# Microscope_LED_Ring_Light.net
KiCad netlist of a schematic drawn in EAGLE
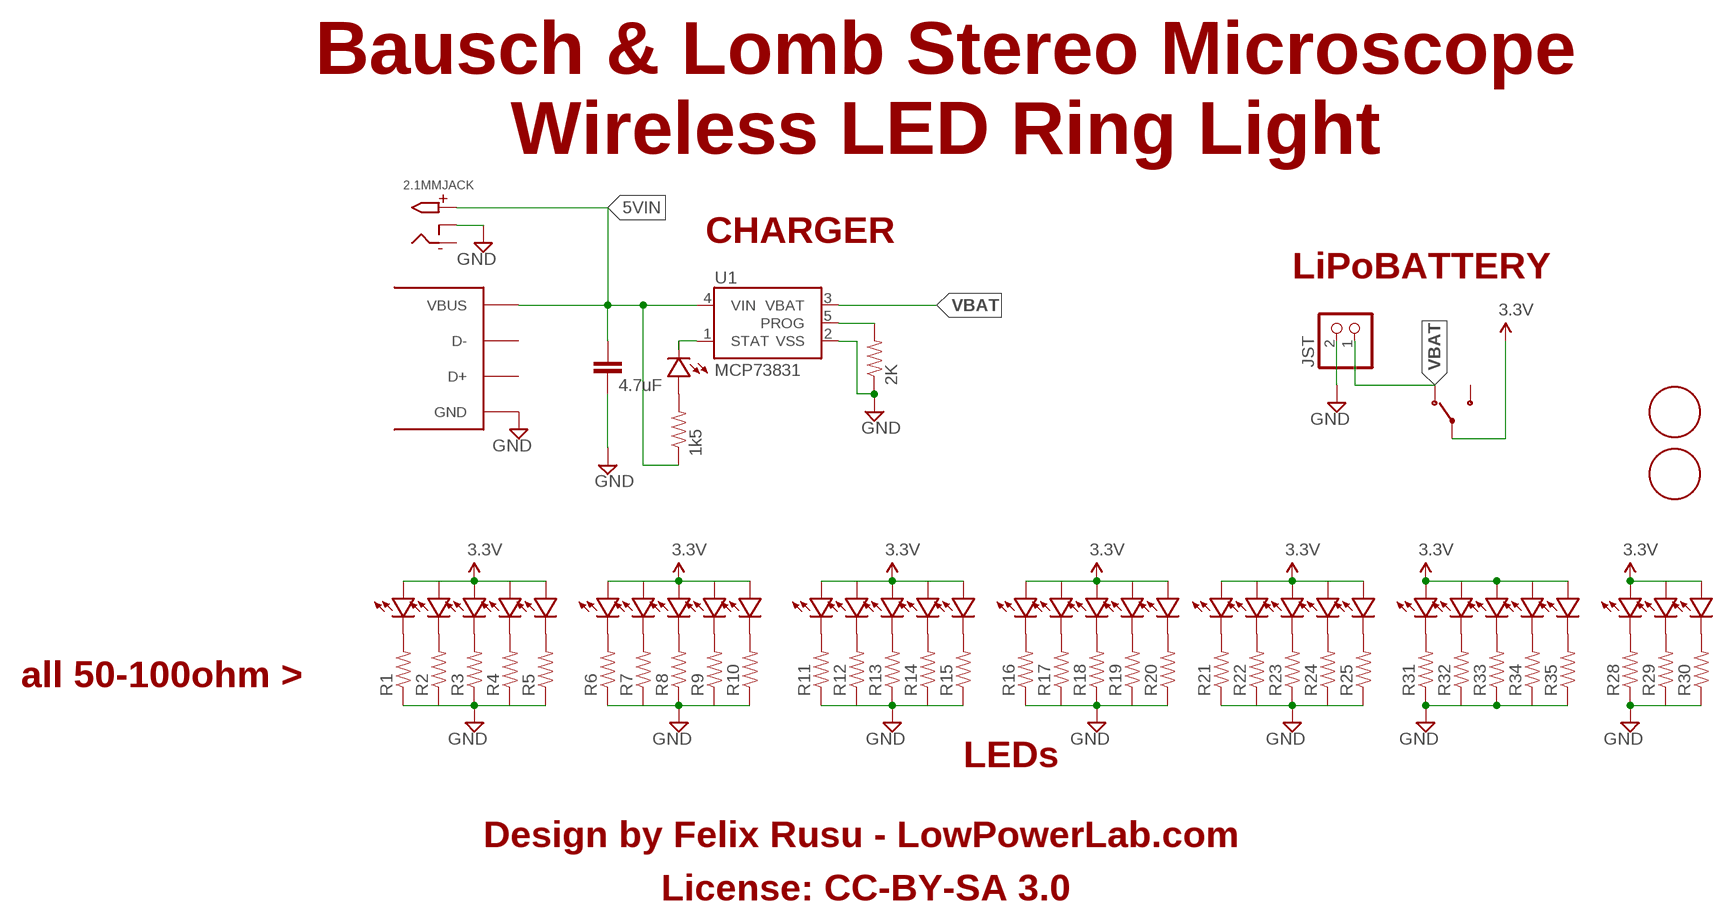
[diagram p0: schematic, sheet 1]

(export (version "E")
  (design (tool "Eeschema 10.0.6"))
  (components
    (comp (ref "2.1MMJACK")
      (value "2.1MMJACKSLOTS")
      (footprint "eagle-import:2.1MM_JACK_SLOTS")
      (libsource (lib "eagle-import") (part "2.1MMJACKSLOTS"))
    )
    (comp (ref "C1")
      (value "4.7uF")
      (footprint "eagle-import:0603-CAP")
      (libsource (lib "eagle-import") (part "CAP0603-CAP"))
    )
    (comp (ref "FIDUCIAL_BOTTOMRIGHT")
      (value "FIDUCIAL1.5MM")
      (footprint "eagle-import:FIDUCIAL_1.5MM")
      (libsource (lib "eagle-import") (part "FIDUCIAL1.5MM"))
    )
    (comp (ref "FIDUCIAL_TOPLEFT")
      (value "FIDUCIAL1.5MM")
      (footprint "eagle-import:FIDUCIAL_1.5MM")
      (libsource (lib "eagle-import") (part "FIDUCIAL1.5MM"))
    )
    (comp (ref "JST")
      (value "JST_2PIN-SMT-RA")
      (footprint "eagle-import:JST-PH-2-SMT-RA")
      (libsource (lib "eagle-import") (part "JST_2PIN-SMT-RA"))
    )
    (comp (ref "R1")
      (value "RESISTOR0805")
      (footprint "eagle-import:0805")
      (libsource (lib "eagle-import") (part "RESISTOR0805"))
    )
    (comp (ref "R2")
      (value "RESISTOR0805")
      (footprint "eagle-import:0805")
      (libsource (lib "eagle-import") (part "RESISTOR0805"))
    )
    (comp (ref "R3")
      (value "RESISTOR0805")
      (footprint "eagle-import:0805")
      (libsource (lib "eagle-import") (part "RESISTOR0805"))
    )
    (comp (ref "R4")
      (value "RESISTOR0805")
      (footprint "eagle-import:0805")
      (libsource (lib "eagle-import") (part "RESISTOR0805"))
    )
    (comp (ref "R5")
      (value "RESISTOR0805")
      (footprint "eagle-import:0805")
      (libsource (lib "eagle-import") (part "RESISTOR0805"))
    )
    (comp (ref "R6")
      (value "RESISTOR0805")
      (footprint "eagle-import:0805")
      (libsource (lib "eagle-import") (part "RESISTOR0805"))
    )
    (comp (ref "R7")
      (value "RESISTOR0805")
      (footprint "eagle-import:0805")
      (libsource (lib "eagle-import") (part "RESISTOR0805"))
    )
    (comp (ref "R8")
      (value "RESISTOR0805")
      (footprint "eagle-import:0805")
      (libsource (lib "eagle-import") (part "RESISTOR0805"))
    )
    (comp (ref "R9")
      (value "RESISTOR0805")
      (footprint "eagle-import:0805")
      (libsource (lib "eagle-import") (part "RESISTOR0805"))
    )
    (comp (ref "R10")
      (value "RESISTOR0805")
      (footprint "eagle-import:0805")
      (libsource (lib "eagle-import") (part "RESISTOR0805"))
    )
    (comp (ref "R11")
      (value "RESISTOR0805")
      (footprint "eagle-import:0805")
      (libsource (lib "eagle-import") (part "RESISTOR0805"))
    )
    (comp (ref "R12")
      (value "RESISTOR0805")
      (footprint "eagle-import:0805")
      (libsource (lib "eagle-import") (part "RESISTOR0805"))
    )
    (comp (ref "R13")
      (value "RESISTOR0805")
      (footprint "eagle-import:0805")
      (libsource (lib "eagle-import") (part "RESISTOR0805"))
    )
    (comp (ref "R14")
      (value "RESISTOR0805")
      (footprint "eagle-import:0805")
      (libsource (lib "eagle-import") (part "RESISTOR0805"))
    )
    (comp (ref "R15")
      (value "RESISTOR0805")
      (footprint "eagle-import:0805")
      (libsource (lib "eagle-import") (part "RESISTOR0805"))
    )
    (comp (ref "R16")
      (value "RESISTOR0805")
      (footprint "eagle-import:0805")
      (libsource (lib "eagle-import") (part "RESISTOR0805"))
    )
    (comp (ref "R17")
      (value "RESISTOR0805")
      (footprint "eagle-import:0805")
      (libsource (lib "eagle-import") (part "RESISTOR0805"))
    )
    (comp (ref "R18")
      (value "RESISTOR0805")
      (footprint "eagle-import:0805")
      (libsource (lib "eagle-import") (part "RESISTOR0805"))
    )
    (comp (ref "R19")
      (value "RESISTOR0805")
      (footprint "eagle-import:0805")
      (libsource (lib "eagle-import") (part "RESISTOR0805"))
    )
    (comp (ref "R20")
      (value "RESISTOR0805")
      (footprint "eagle-import:0805")
      (libsource (lib "eagle-import") (part "RESISTOR0805"))
    )
    (comp (ref "R21")
      (value "RESISTOR0805")
      (footprint "eagle-import:0805")
      (libsource (lib "eagle-import") (part "RESISTOR0805"))
    )
    (comp (ref "R22")
      (value "RESISTOR0805")
      (footprint "eagle-import:0805")
      (libsource (lib "eagle-import") (part "RESISTOR0805"))
    )
    (comp (ref "R23")
      (value "RESISTOR0805")
      (footprint "eagle-import:0805")
      (libsource (lib "eagle-import") (part "RESISTOR0805"))
    )
    (comp (ref "R24")
      (value "RESISTOR0805")
      (footprint "eagle-import:0805")
      (libsource (lib "eagle-import") (part "RESISTOR0805"))
    )
    (comp (ref "R25")
      (value "RESISTOR0805")
      (footprint "eagle-import:0805")
      (libsource (lib "eagle-import") (part "RESISTOR0805"))
    )
    (comp (ref "R26")
      (value "1k5")
      (footprint "eagle-import:0603-RES")
      (libsource (lib "eagle-import") (part "RESISTOR0603-RES"))
    )
    (comp (ref "R27")
      (value "2K")
      (footprint "eagle-import:0603-RES")
      (libsource (lib "eagle-import") (part "RESISTOR0603-RES"))
    )
    (comp (ref "R28")
      (value "RESISTOR0805")
      (footprint "eagle-import:0805")
      (libsource (lib "eagle-import") (part "RESISTOR0805"))
    )
    (comp (ref "R29")
      (value "RESISTOR0805")
      (footprint "eagle-import:0805")
      (libsource (lib "eagle-import") (part "RESISTOR0805"))
    )
    (comp (ref "R30")
      (value "RESISTOR0805")
      (footprint "eagle-import:0805")
      (libsource (lib "eagle-import") (part "RESISTOR0805"))
    )
    (comp (ref "R31")
      (value "RESISTOR0805")
      (footprint "eagle-import:0805")
      (libsource (lib "eagle-import") (part "RESISTOR0805"))
    )
    (comp (ref "R32")
      (value "RESISTOR0805")
      (footprint "eagle-import:0805")
      (libsource (lib "eagle-import") (part "RESISTOR0805"))
    )
    (comp (ref "R33")
      (value "RESISTOR0805")
      (footprint "eagle-import:0805")
      (libsource (lib "eagle-import") (part "RESISTOR0805"))
    )
    (comp (ref "R34")
      (value "RESISTOR0805")
      (footprint "eagle-import:0805")
      (libsource (lib "eagle-import") (part "RESISTOR0805"))
    )
    (comp (ref "R35")
      (value "RESISTOR0805")
      (footprint "eagle-import:0805")
      (libsource (lib "eagle-import") (part "RESISTOR0805"))
    )
    (comp (ref "U$1")
      (value "LED")
      (footprint "eagle-import:LED_2.8X3.3MM")
      (libsource (lib "eagle-import") (part "LED"))
    )
    (comp (ref "U$2")
      (value "LED")
      (footprint "eagle-import:LED_2.8X3.3MM")
      (libsource (lib "eagle-import") (part "LED"))
    )
    (comp (ref "U$3")
      (value "LED")
      (footprint "eagle-import:LED_2.8X3.3MM")
      (libsource (lib "eagle-import") (part "LED"))
    )
    (comp (ref "U$4")
      (value "LED")
      (footprint "eagle-import:LED_2.8X3.3MM")
      (libsource (lib "eagle-import") (part "LED"))
    )
    (comp (ref "U$5")
      (value "LED")
      (footprint "eagle-import:LED_2.8X3.3MM")
      (libsource (lib "eagle-import") (part "LED"))
    )
    (comp (ref "U$6")
      (value "LED")
      (footprint "eagle-import:LED_2.8X3.3MM")
      (libsource (lib "eagle-import") (part "LED"))
    )
    (comp (ref "U$7")
      (value "LED")
      (footprint "eagle-import:LED_2.8X3.3MM")
      (libsource (lib "eagle-import") (part "LED"))
    )
    (comp (ref "U$8")
      (value "LED")
      (footprint "eagle-import:LED_2.8X3.3MM")
      (libsource (lib "eagle-import") (part "LED"))
    )
    (comp (ref "U$9")
      (value "LED")
      (footprint "eagle-import:LED_2.8X3.3MM")
      (libsource (lib "eagle-import") (part "LED"))
    )
    (comp (ref "U$10")
      (value "LED")
      (footprint "eagle-import:LED_2.8X3.3MM")
      (libsource (lib "eagle-import") (part "LED"))
    )
    (comp (ref "U$11")
      (value "LED")
      (footprint "eagle-import:LED_2.8X3.3MM")
      (libsource (lib "eagle-import") (part "LED"))
    )
    (comp (ref "U$12")
      (value "LED")
      (footprint "eagle-import:LED_2.8X3.3MM")
      (libsource (lib "eagle-import") (part "LED"))
    )
    (comp (ref "U$13")
      (value "LED")
      (footprint "eagle-import:LED_2.8X3.3MM")
      (libsource (lib "eagle-import") (part "LED"))
    )
    (comp (ref "U$14")
      (value "LED")
      (footprint "eagle-import:LED_2.8X3.3MM")
      (libsource (lib "eagle-import") (part "LED"))
    )
    (comp (ref "U$15")
      (value "LED")
      (footprint "eagle-import:LED_2.8X3.3MM")
      (libsource (lib "eagle-import") (part "LED"))
    )
    (comp (ref "U$16")
      (value "LED")
      (footprint "eagle-import:LED_2.8X3.3MM")
      (libsource (lib "eagle-import") (part "LED"))
    )
    (comp (ref "U$17")
      (value "LED")
      (footprint "eagle-import:LED_2.8X3.3MM")
      (libsource (lib "eagle-import") (part "LED"))
    )
    (comp (ref "U$18")
      (value "LED")
      (footprint "eagle-import:LED_2.8X3.3MM")
      (libsource (lib "eagle-import") (part "LED"))
    )
    (comp (ref "U$19")
      (value "LED")
      (footprint "eagle-import:LED_2.8X3.3MM")
      (libsource (lib "eagle-import") (part "LED"))
    )
    (comp (ref "U$20")
      (value "LED")
      (footprint "eagle-import:LED_2.8X3.3MM")
      (libsource (lib "eagle-import") (part "LED"))
    )
    (comp (ref "U$21")
      (value "LED")
      (footprint "eagle-import:LED_2.8X3.3MM")
      (libsource (lib "eagle-import") (part "LED"))
    )
    (comp (ref "U$22")
      (value "LED")
      (footprint "eagle-import:LED_2.8X3.3MM")
      (libsource (lib "eagle-import") (part "LED"))
    )
    (comp (ref "U$23")
      (value "LED")
      (footprint "eagle-import:LED_2.8X3.3MM")
      (libsource (lib "eagle-import") (part "LED"))
    )
    (comp (ref "U$24")
      (value "LED")
      (footprint "eagle-import:LED_2.8X3.3MM")
      (libsource (lib "eagle-import") (part "LED"))
    )
    (comp (ref "U$25")
      (value "LED")
      (footprint "eagle-import:LED_2.8X3.3MM")
      (libsource (lib "eagle-import") (part "LED"))
    )
    (comp (ref "U$26")
      (value "USB_4PIN2PINS_SLOTTED")
      (footprint "eagle-import:USB-B-MICRO_2PADS_SLOTS")
      (libsource (lib "eagle-import") (part "USB_4PIN2PINS_SLOTTED"))
    )
    (comp (ref "U$27")
      (value "SWITCH_SPDT")
      (footprint "eagle-import:SWITCH-SPDT_CKN9560")
      (libsource (lib "eagle-import") (part "SWITCH_SPDT"))
    )
    (comp (ref "U$28")
      (value "LED0603")
      (footprint "eagle-import:0603-LED")
      (libsource (lib "eagle-import") (part "LED0603"))
    )
    (comp (ref "U$29")
      (value "LED")
      (footprint "eagle-import:LED_2.8X3.3MM")
      (libsource (lib "eagle-import") (part "LED"))
    )
    (comp (ref "U$30")
      (value "LED")
      (footprint "eagle-import:LED_2.8X3.3MM")
      (libsource (lib "eagle-import") (part "LED"))
    )
    (comp (ref "U$31")
      (value "LED")
      (footprint "eagle-import:LED_2.8X3.3MM")
      (libsource (lib "eagle-import") (part "LED"))
    )
    (comp (ref "U$32")
      (value "LED")
      (footprint "eagle-import:LED_2.8X3.3MM")
      (libsource (lib "eagle-import") (part "LED"))
    )
    (comp (ref "U$33")
      (value "LED")
      (footprint "eagle-import:LED_2.8X3.3MM")
      (libsource (lib "eagle-import") (part "LED"))
    )
    (comp (ref "U$34")
      (value "LED")
      (footprint "eagle-import:LED_2.8X3.3MM")
      (libsource (lib "eagle-import") (part "LED"))
    )
    (comp (ref "U$35")
      (value "LED")
      (footprint "eagle-import:LED_2.8X3.3MM")
      (libsource (lib "eagle-import") (part "LED"))
    )
    (comp (ref "U$36")
      (value "LED")
      (footprint "eagle-import:LED_2.8X3.3MM")
      (libsource (lib "eagle-import") (part "LED"))
    )
    (comp (ref "U1")
      (value "MCP73831")
      (footprint "eagle-import:SOT23-5")
      (libsource (lib "eagle-import") (part "MCP73831"))
    )
  )
  (nets
    (net (code "1") (name "3.3V") (class "Default")
      (node (ref "U$1") (pin "PLUS") (pinfunction "PLUS_PLUS") (pintype "passive"))
      (node (ref "U$10") (pin "PLUS") (pinfunction "PLUS_PLUS") (pintype "passive"))
      (node (ref "U$11") (pin "PLUS") (pinfunction "PLUS_PLUS") (pintype "passive"))
      (node (ref "U$12") (pin "PLUS") (pinfunction "PLUS_PLUS") (pintype "passive"))
      (node (ref "U$13") (pin "PLUS") (pinfunction "PLUS_PLUS") (pintype "passive"))
      (node (ref "U$14") (pin "PLUS") (pinfunction "PLUS_PLUS") (pintype "passive"))
      (node (ref "U$15") (pin "PLUS") (pinfunction "PLUS_PLUS") (pintype "passive"))
      (node (ref "U$16") (pin "PLUS") (pinfunction "PLUS_PLUS") (pintype "passive"))
      (node (ref "U$17") (pin "PLUS") (pinfunction "PLUS_PLUS") (pintype "passive"))
      (node (ref "U$18") (pin "PLUS") (pinfunction "PLUS_PLUS") (pintype "passive"))
      (node (ref "U$19") (pin "PLUS") (pinfunction "PLUS_PLUS") (pintype "passive"))
      (node (ref "U$2") (pin "PLUS") (pinfunction "PLUS_PLUS") (pintype "passive"))
      (node (ref "U$20") (pin "PLUS") (pinfunction "PLUS_PLUS") (pintype "passive"))
      (node (ref "U$21") (pin "PLUS") (pinfunction "PLUS_PLUS") (pintype "passive"))
      (node (ref "U$22") (pin "PLUS") (pinfunction "PLUS_PLUS") (pintype "passive"))
      (node (ref "U$23") (pin "PLUS") (pinfunction "PLUS_PLUS") (pintype "passive"))
      (node (ref "U$24") (pin "PLUS") (pinfunction "PLUS_PLUS") (pintype "passive"))
      (node (ref "U$25") (pin "PLUS") (pinfunction "PLUS_PLUS") (pintype "passive"))
      (node (ref "U$27") (pin "2") (pinfunction "2_2") (pintype "bidirectional"))
      (node (ref "U$29") (pin "PLUS") (pinfunction "PLUS_PLUS") (pintype "passive"))
      (node (ref "U$3") (pin "PLUS") (pinfunction "PLUS_PLUS") (pintype "passive"))
      (node (ref "U$30") (pin "PLUS") (pinfunction "PLUS_PLUS") (pintype "passive"))
      (node (ref "U$31") (pin "PLUS") (pinfunction "PLUS_PLUS") (pintype "passive"))
      (node (ref "U$32") (pin "PLUS") (pinfunction "PLUS_PLUS") (pintype "passive"))
      (node (ref "U$33") (pin "PLUS") (pinfunction "PLUS_PLUS") (pintype "passive"))
      (node (ref "U$34") (pin "PLUS") (pinfunction "PLUS_PLUS") (pintype "passive"))
      (node (ref "U$35") (pin "PLUS") (pinfunction "PLUS_PLUS") (pintype "passive"))
      (node (ref "U$36") (pin "PLUS") (pinfunction "PLUS_PLUS") (pintype "passive"))
      (node (ref "U$4") (pin "PLUS") (pinfunction "PLUS_PLUS") (pintype "passive"))
      (node (ref "U$5") (pin "PLUS") (pinfunction "PLUS_PLUS") (pintype "passive"))
      (node (ref "U$6") (pin "PLUS") (pinfunction "PLUS_PLUS") (pintype "passive"))
      (node (ref "U$7") (pin "PLUS") (pinfunction "PLUS_PLUS") (pintype "passive"))
      (node (ref "U$8") (pin "PLUS") (pinfunction "PLUS_PLUS") (pintype "passive"))
      (node (ref "U$9") (pin "PLUS") (pinfunction "PLUS_PLUS") (pintype "passive"))
    )
    (net (code "2") (name "5VIN") (class "Default")
      (node (ref "2.1MMJACK") (pin "TIP") (pinfunction "TIP_TIP") (pintype "bidirectional"))
      (node (ref "C1") (pin "1") (pinfunction "1_1") (pintype "passive"))
      (node (ref "R26") (pin "1") (pinfunction "1_1") (pintype "passive"))
      (node (ref "U$26") (pin "VBUS") (pinfunction "VBUS_VBUS") (pintype "bidirectional"))
      (node (ref "U1") (pin "4") (pinfunction "VIN_4") (pintype "power_in"))
    )
    (net (code "3") (name "GND") (class "Default")
      (node (ref "2.1MMJACK") (pin "SIDE") (pinfunction "RING_SW_SIDE") (pintype "bidirectional"))
      (node (ref "C1") (pin "2") (pinfunction "2_2") (pintype "passive"))
      (node (ref "JST") (pin "2") (pinfunction "1_2") (pintype "passive"))
      (node (ref "R1") (pin "1") (pinfunction "1_1") (pintype "passive"))
      (node (ref "R10") (pin "1") (pinfunction "1_1") (pintype "passive"))
      (node (ref "R11") (pin "1") (pinfunction "1_1") (pintype "passive"))
      (node (ref "R12") (pin "1") (pinfunction "1_1") (pintype "passive"))
      (node (ref "R13") (pin "1") (pinfunction "1_1") (pintype "passive"))
      (node (ref "R14") (pin "1") (pinfunction "1_1") (pintype "passive"))
      (node (ref "R15") (pin "1") (pinfunction "1_1") (pintype "passive"))
      (node (ref "R16") (pin "1") (pinfunction "1_1") (pintype "passive"))
      (node (ref "R17") (pin "1") (pinfunction "1_1") (pintype "passive"))
      (node (ref "R18") (pin "1") (pinfunction "1_1") (pintype "passive"))
      (node (ref "R19") (pin "1") (pinfunction "1_1") (pintype "passive"))
      (node (ref "R2") (pin "1") (pinfunction "1_1") (pintype "passive"))
      (node (ref "R20") (pin "1") (pinfunction "1_1") (pintype "passive"))
      (node (ref "R21") (pin "1") (pinfunction "1_1") (pintype "passive"))
      (node (ref "R22") (pin "1") (pinfunction "1_1") (pintype "passive"))
      (node (ref "R23") (pin "1") (pinfunction "1_1") (pintype "passive"))
      (node (ref "R24") (pin "1") (pinfunction "1_1") (pintype "passive"))
      (node (ref "R25") (pin "1") (pinfunction "1_1") (pintype "passive"))
      (node (ref "R27") (pin "1") (pinfunction "1_1") (pintype "passive"))
      (node (ref "R28") (pin "1") (pinfunction "1_1") (pintype "passive"))
      (node (ref "R29") (pin "1") (pinfunction "1_1") (pintype "passive"))
      (node (ref "R3") (pin "1") (pinfunction "1_1") (pintype "passive"))
      (node (ref "R30") (pin "1") (pinfunction "1_1") (pintype "passive"))
      (node (ref "R31") (pin "1") (pinfunction "1_1") (pintype "passive"))
      (node (ref "R32") (pin "1") (pinfunction "1_1") (pintype "passive"))
      (node (ref "R33") (pin "1") (pinfunction "1_1") (pintype "passive"))
      (node (ref "R34") (pin "1") (pinfunction "1_1") (pintype "passive"))
      (node (ref "R35") (pin "1") (pinfunction "1_1") (pintype "passive"))
      (node (ref "R4") (pin "1") (pinfunction "1_1") (pintype "passive"))
      (node (ref "R5") (pin "1") (pinfunction "1_1") (pintype "passive"))
      (node (ref "R6") (pin "1") (pinfunction "1_1") (pintype "passive"))
      (node (ref "R7") (pin "1") (pinfunction "1_1") (pintype "passive"))
      (node (ref "R8") (pin "1") (pinfunction "1_1") (pintype "passive"))
      (node (ref "R9") (pin "1") (pinfunction "1_1") (pintype "passive"))
      (node (ref "U$26") (pin "GND") (pinfunction "GND_GND") (pintype "bidirectional"))
      (node (ref "U1") (pin "2") (pinfunction "VSS_2") (pintype "power_in"))
    )
    (net (code "4") (name "Net-(R1-Pad2)") (class "Default")
      (node (ref "R1") (pin "2") (pinfunction "2_2") (pintype "passive"))
      (node (ref "U$3") (pin "MINUS") (pinfunction "MINUS_MINUS") (pintype "passive"))
    )
    (net (code "5") (name "Net-(R2-Pad2)") (class "Default")
      (node (ref "R2") (pin "2") (pinfunction "2_2") (pintype "passive"))
      (node (ref "U$4") (pin "MINUS") (pinfunction "MINUS_MINUS") (pintype "passive"))
    )
    (net (code "6") (name "Net-(R3-Pad2)") (class "Default")
      (node (ref "R3") (pin "2") (pinfunction "2_2") (pintype "passive"))
      (node (ref "U$5") (pin "MINUS") (pinfunction "MINUS_MINUS") (pintype "passive"))
    )
    (net (code "7") (name "Net-(R4-Pad2)") (class "Default")
      (node (ref "R4") (pin "2") (pinfunction "2_2") (pintype "passive"))
      (node (ref "U$6") (pin "MINUS") (pinfunction "MINUS_MINUS") (pintype "passive"))
    )
    (net (code "8") (name "Net-(R5-Pad2)") (class "Default")
      (node (ref "R5") (pin "2") (pinfunction "2_2") (pintype "passive"))
      (node (ref "U$7") (pin "MINUS") (pinfunction "MINUS_MINUS") (pintype "passive"))
    )
    (net (code "9") (name "Net-(R6-Pad2)") (class "Default")
      (node (ref "R6") (pin "2") (pinfunction "2_2") (pintype "passive"))
      (node (ref "U$1") (pin "MINUS") (pinfunction "MINUS_MINUS") (pintype "passive"))
    )
    (net (code "10") (name "Net-(R7-Pad2)") (class "Default")
      (node (ref "R7") (pin "2") (pinfunction "2_2") (pintype "passive"))
      (node (ref "U$2") (pin "MINUS") (pinfunction "MINUS_MINUS") (pintype "passive"))
    )
    (net (code "11") (name "Net-(R8-Pad2)") (class "Default")
      (node (ref "R8") (pin "2") (pinfunction "2_2") (pintype "passive"))
      (node (ref "U$8") (pin "MINUS") (pinfunction "MINUS_MINUS") (pintype "passive"))
    )
    (net (code "12") (name "Net-(R9-Pad2)") (class "Default")
      (node (ref "R9") (pin "2") (pinfunction "2_2") (pintype "passive"))
      (node (ref "U$9") (pin "MINUS") (pinfunction "MINUS_MINUS") (pintype "passive"))
    )
    (net (code "13") (name "Net-(R10-Pad2)") (class "Default")
      (node (ref "R10") (pin "2") (pinfunction "2_2") (pintype "passive"))
      (node (ref "U$10") (pin "MINUS") (pinfunction "MINUS_MINUS") (pintype "passive"))
    )
    (net (code "14") (name "Net-(R11-Pad2)") (class "Default")
      (node (ref "R11") (pin "2") (pinfunction "2_2") (pintype "passive"))
      (node (ref "U$11") (pin "MINUS") (pinfunction "MINUS_MINUS") (pintype "passive"))
    )
    (net (code "15") (name "Net-(R12-Pad2)") (class "Default")
      (node (ref "R12") (pin "2") (pinfunction "2_2") (pintype "passive"))
      (node (ref "U$12") (pin "MINUS") (pinfunction "MINUS_MINUS") (pintype "passive"))
    )
    (net (code "16") (name "Net-(R13-Pad2)") (class "Default")
      (node (ref "R13") (pin "2") (pinfunction "2_2") (pintype "passive"))
      (node (ref "U$13") (pin "MINUS") (pinfunction "MINUS_MINUS") (pintype "passive"))
    )
    (net (code "17") (name "Net-(R14-Pad2)") (class "Default")
      (node (ref "R14") (pin "2") (pinfunction "2_2") (pintype "passive"))
      (node (ref "U$14") (pin "MINUS") (pinfunction "MINUS_MINUS") (pintype "passive"))
    )
    (net (code "18") (name "Net-(R15-Pad2)") (class "Default")
      (node (ref "R15") (pin "2") (pinfunction "2_2") (pintype "passive"))
      (node (ref "U$15") (pin "MINUS") (pinfunction "MINUS_MINUS") (pintype "passive"))
    )
    (net (code "19") (name "Net-(R16-Pad2)") (class "Default")
      (node (ref "R16") (pin "2") (pinfunction "2_2") (pintype "passive"))
      (node (ref "U$16") (pin "MINUS") (pinfunction "MINUS_MINUS") (pintype "passive"))
    )
    (net (code "20") (name "Net-(R17-Pad2)") (class "Default")
      (node (ref "R17") (pin "2") (pinfunction "2_2") (pintype "passive"))
      (node (ref "U$17") (pin "MINUS") (pinfunction "MINUS_MINUS") (pintype "passive"))
    )
    (net (code "21") (name "Net-(R18-Pad2)") (class "Default")
      (node (ref "R18") (pin "2") (pinfunction "2_2") (pintype "passive"))
      (node (ref "U$18") (pin "MINUS") (pinfunction "MINUS_MINUS") (pintype "passive"))
    )
    (net (code "22") (name "Net-(R19-Pad2)") (class "Default")
      (node (ref "R19") (pin "2") (pinfunction "2_2") (pintype "passive"))
      (node (ref "U$19") (pin "MINUS") (pinfunction "MINUS_MINUS") (pintype "passive"))
    )
    (net (code "23") (name "Net-(R20-Pad2)") (class "Default")
      (node (ref "R20") (pin "2") (pinfunction "2_2") (pintype "passive"))
      (node (ref "U$20") (pin "MINUS") (pinfunction "MINUS_MINUS") (pintype "passive"))
    )
    (net (code "24") (name "Net-(R21-Pad2)") (class "Default")
      (node (ref "R21") (pin "2") (pinfunction "2_2") (pintype "passive"))
      (node (ref "U$21") (pin "MINUS") (pinfunction "MINUS_MINUS") (pintype "passive"))
    )
    (net (code "25") (name "Net-(R22-Pad2)") (class "Default")
      (node (ref "R22") (pin "2") (pinfunction "2_2") (pintype "passive"))
      (node (ref "U$22") (pin "MINUS") (pinfunction "MINUS_MINUS") (pintype "passive"))
    )
    (net (code "26") (name "Net-(R23-Pad2)") (class "Default")
      (node (ref "R23") (pin "2") (pinfunction "2_2") (pintype "passive"))
      (node (ref "U$23") (pin "MINUS") (pinfunction "MINUS_MINUS") (pintype "passive"))
    )
    (net (code "27") (name "Net-(R24-Pad2)") (class "Default")
      (node (ref "R24") (pin "2") (pinfunction "2_2") (pintype "passive"))
      (node (ref "U$24") (pin "MINUS") (pinfunction "MINUS_MINUS") (pintype "passive"))
    )
    (net (code "28") (name "Net-(R25-Pad2)") (class "Default")
      (node (ref "R25") (pin "2") (pinfunction "2_2") (pintype "passive"))
      (node (ref "U$25") (pin "MINUS") (pinfunction "MINUS_MINUS") (pintype "passive"))
    )
    (net (code "29") (name "Net-(R26-Pad2)") (class "Default")
      (node (ref "R26") (pin "2") (pinfunction "2_2") (pintype "passive"))
      (node (ref "U$28") (pin "PLUS") (pinfunction "PLUS_PLUS") (pintype "passive"))
    )
    (net (code "30") (name "Net-(R28-Pad2)") (class "Default")
      (node (ref "R28") (pin "2") (pinfunction "2_2") (pintype "passive"))
      (node (ref "U$29") (pin "MINUS") (pinfunction "MINUS_MINUS") (pintype "passive"))
    )
    (net (code "31") (name "Net-(R29-Pad2)") (class "Default")
      (node (ref "R29") (pin "2") (pinfunction "2_2") (pintype "passive"))
      (node (ref "U$30") (pin "MINUS") (pinfunction "MINUS_MINUS") (pintype "passive"))
    )
    (net (code "32") (name "Net-(R30-Pad2)") (class "Default")
      (node (ref "R30") (pin "2") (pinfunction "2_2") (pintype "passive"))
      (node (ref "U$31") (pin "MINUS") (pinfunction "MINUS_MINUS") (pintype "passive"))
    )
    (net (code "33") (name "Net-(R31-Pad2)") (class "Default")
      (node (ref "R31") (pin "2") (pinfunction "2_2") (pintype "passive"))
      (node (ref "U$32") (pin "MINUS") (pinfunction "MINUS_MINUS") (pintype "passive"))
    )
    (net (code "34") (name "Net-(R32-Pad2)") (class "Default")
      (node (ref "R32") (pin "2") (pinfunction "2_2") (pintype "passive"))
      (node (ref "U$33") (pin "MINUS") (pinfunction "MINUS_MINUS") (pintype "passive"))
    )
    (net (code "35") (name "Net-(R33-Pad2)") (class "Default")
      (node (ref "R33") (pin "2") (pinfunction "2_2") (pintype "passive"))
      (node (ref "U$34") (pin "MINUS") (pinfunction "MINUS_MINUS") (pintype "passive"))
    )
    (net (code "36") (name "Net-(R34-Pad2)") (class "Default")
      (node (ref "R34") (pin "2") (pinfunction "2_2") (pintype "passive"))
      (node (ref "U$35") (pin "MINUS") (pinfunction "MINUS_MINUS") (pintype "passive"))
    )
    (net (code "37") (name "Net-(R35-Pad2)") (class "Default")
      (node (ref "R35") (pin "2") (pinfunction "2_2") (pintype "passive"))
      (node (ref "U$36") (pin "MINUS") (pinfunction "MINUS_MINUS") (pintype "passive"))
    )
    (net (code "38") (name "Net-(U1-PROG)") (class "Default")
      (node (ref "R27") (pin "2") (pinfunction "2_2") (pintype "passive"))
      (node (ref "U1") (pin "5") (pinfunction "PROG_5") (pintype "input"))
    )
    (net (code "39") (name "Net-(U1-STAT)") (class "Default")
      (node (ref "U$28") (pin "MINUS") (pinfunction "MINUS_MINUS") (pintype "passive"))
      (node (ref "U1") (pin "1") (pinfunction "STAT_1") (pintype "output"))
    )
    (net (code "40") (name "VBAT") (class "Default")
      (node (ref "JST") (pin "1") (pinfunction "2_1") (pintype "passive"))
      (node (ref "U$27") (pin "1") (pinfunction "1_1") (pintype "bidirectional"))
      (node (ref "U1") (pin "3") (pinfunction "VBAT_3") (pintype "power_in"))
    )
    (net (code "41") (name "unconnected-(2.1MMJACK-PadRING)") (class "Default")
      (node (ref "2.1MMJACK") (pin "RING") (pinfunction "RING_RING") (pintype "bidirectional"))
    )
    (net (code "42") (name "unconnected-(FIDUCIAL_BOTTOMRIGHT-FIDUCIAL-PadP$1)") (class "Default")
      (node (ref "FIDUCIAL_BOTTOMRIGHT") (pin "P$1") (pinfunction "FIDUCIAL_P$1") (pintype "bidirectional"))
    )
    (net (code "43") (name "unconnected-(FIDUCIAL_TOPLEFT-FIDUCIAL-PadP$1)") (class "Default")
      (node (ref "FIDUCIAL_TOPLEFT") (pin "P$1") (pinfunction "FIDUCIAL_P$1") (pintype "bidirectional"))
    )
    (net (code "44") (name "unconnected-(U$26-D+-PadMT1)") (class "Default")
      (node (ref "U$26") (pin "MT1") (pinfunction "D+_MT1") (pintype "bidirectional"))
    )
    (net (code "45") (name "unconnected-(U$26-D--PadMT2)") (class "Default")
      (node (ref "U$26") (pin "MT2") (pinfunction "D-_MT2") (pintype "bidirectional"))
    )
    (net (code "46") (name "unconnected-(U$27-Pad3)") (class "Default")
      (node (ref "U$27") (pin "3") (pinfunction "3_3") (pintype "bidirectional"))
    )
  )
)
